# CAN_arduino_shield.net
KiCad netlist of a schematic drawn in EAGLE
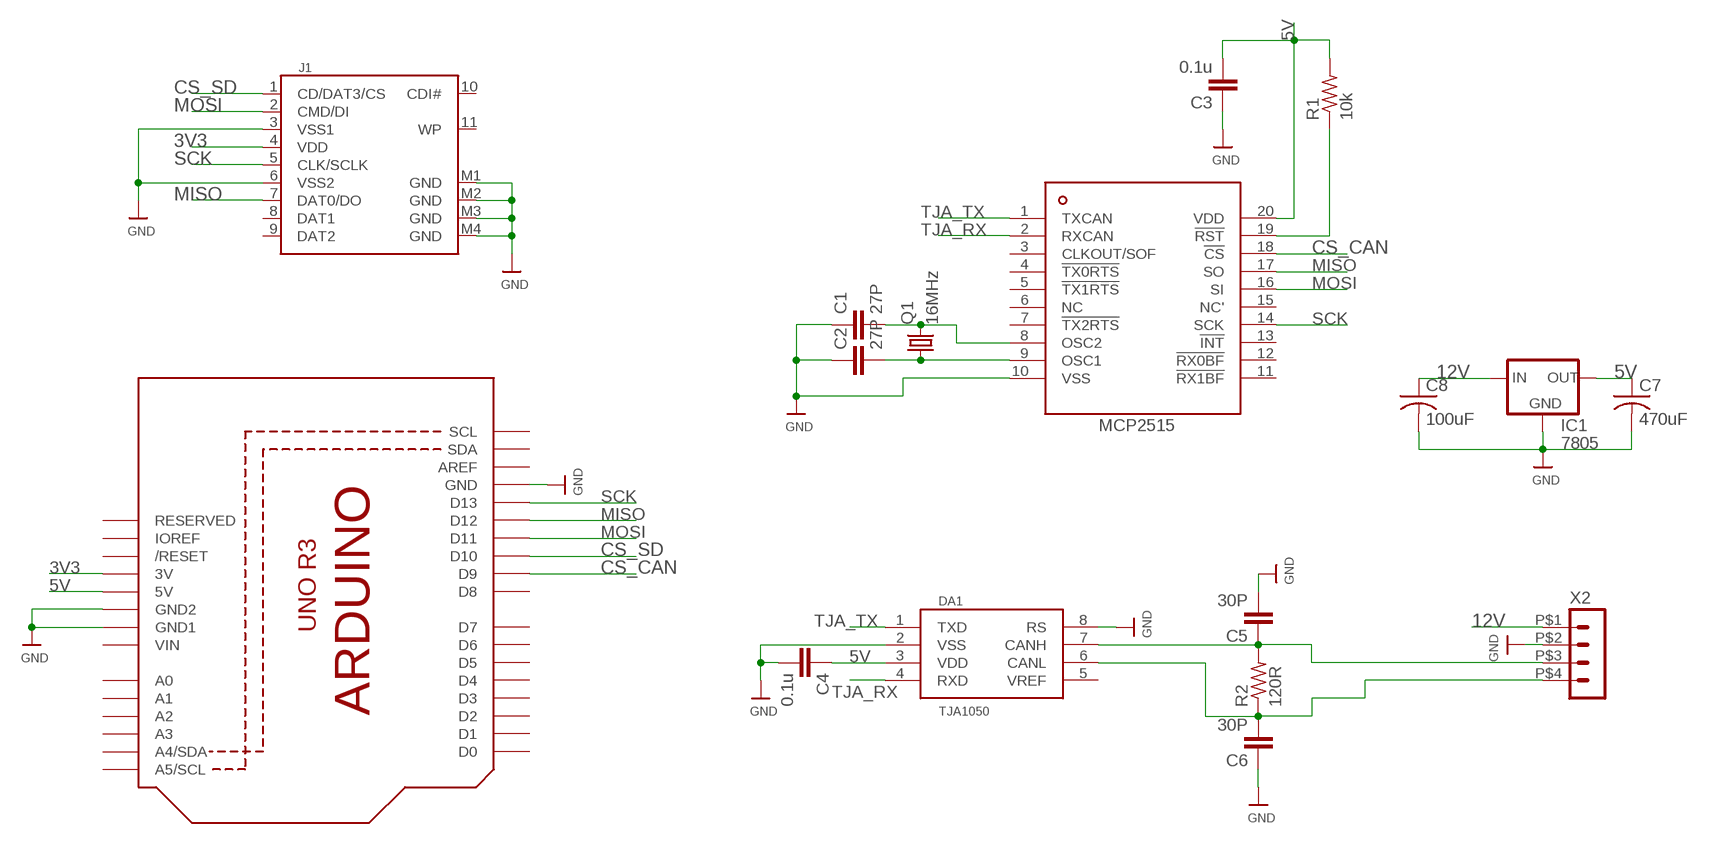
[diagram p0: schematic, sheet 1]

(export (version "E")
  (design (tool "Eeschema 10.0.6"))
  (components
    (comp (ref "C1")
      (value "27P")
      (footprint "eagle-import:C0805")
      (libsource (lib "eagle-import") (part "C-EUC0805"))
    )
    (comp (ref "C2")
      (value "27P")
      (footprint "eagle-import:C0805")
      (libsource (lib "eagle-import") (part "C-EUC0805"))
    )
    (comp (ref "C3")
      (value "0.1u")
      (footprint "eagle-import:C0805")
      (libsource (lib "eagle-import") (part "C-EUC0805"))
    )
    (comp (ref "C4")
      (value "0.1u")
      (footprint "eagle-import:C0805")
      (libsource (lib "eagle-import") (part "C-EUC0805"))
    )
    (comp (ref "C5")
      (value "30P")
      (footprint "eagle-import:C0805")
      (libsource (lib "eagle-import") (part "C-EUC0805"))
    )
    (comp (ref "C6")
      (value "30P")
      (footprint "eagle-import:C0805")
      (libsource (lib "eagle-import") (part "C-EUC0805"))
    )
    (comp (ref "C7")
      (value "470uF")
      (footprint "eagle-import:C025-050X050")
      (libsource (lib "eagle-import") (part "C-US025-050X050"))
    )
    (comp (ref "C8")
      (value "100uF")
      (footprint "eagle-import:C025-050X050")
      (libsource (lib "eagle-import") (part "C-US025-050X050"))
    )
    (comp (ref "DA1")
      (value "TJA1050")
      (footprint "eagle-import:SO08")
      (libsource (lib "eagle-import") (part "TJA1050"))
    )
    (comp (ref "IC1")
      (value "7805")
      (footprint "eagle-import:78XXS")
      (libsource (lib "eagle-import") (part "78XXS"))
    )
    (comp (ref "J1")
      (value "SDCARD")
      (footprint "eagle-import:SDCMF-10915W010")
      (libsource (lib "eagle-import") (part "SDCARD"))
    )
    (comp (ref "Q1")
      (value "16MHz")
      (footprint "eagle-import:HC49_S")
      (libsource (lib "eagle-import") (part "CRYSTALHC49S"))
    )
    (comp (ref "R1")
      (value "10k")
      (footprint "eagle-import:M0805")
      (libsource (lib "eagle-import") (part "R-US_M0805"))
    )
    (comp (ref "R2")
      (value "120R")
      (footprint "eagle-import:M0805")
      (libsource (lib "eagle-import") (part "R-US_M0805"))
    )
    (comp (ref "U$1")
      (value "MCP2515")
      (footprint "eagle-import:TSSOP20")
      (libsource (lib "eagle-import") (part "MCP2515"))
    )
    (comp (ref "U1")
      (value "ARDUINOR3-BPLACE")
      (footprint "eagle-import:ARDUINOR3-BPLACE")
      (libsource (lib "eagle-import") (part "ARDUINOR3-BPLACE"))
    )
    (comp (ref "X2")
      (value "HEADER_POS4_43045-0412")
      (footprint "eagle-import:43045-0412")
      (libsource (lib "eagle-import") (part "HEADER_POS4_?43045-0412"))
    )
  )
  (nets
    (net (code "1") (name "/3V3") (class "Default")
      (node (ref "J1") (pin "4") (pinfunction "VDD_4") (pintype "power_in"))
      (node (ref "U1") (pin "3V") (pinfunction "3V_3V") (pintype "power_in"))
    )
    (net (code "2") (name "/5V") (class "Default")
      (node (ref "C3") (pin "2") (pinfunction "2_2") (pintype "passive"))
      (node (ref "C4") (pin "1") (pinfunction "1_1") (pintype "passive"))
      (node (ref "C7") (pin "1") (pinfunction "1_1") (pintype "passive"))
      (node (ref "DA1") (pin "3") (pinfunction "VDD_3") (pintype "power_in"))
      (node (ref "IC1") (pin "OUT") (pinfunction "OUT_OUT") (pintype "passive"))
      (node (ref "R1") (pin "2") (pinfunction "2_2") (pintype "passive"))
      (node (ref "U$1") (pin "20") (pinfunction "VDD_20") (pintype "bidirectional"))
      (node (ref "U1") (pin "5V") (pinfunction "5V_5V") (pintype "power_in"))
    )
    (net (code "3") (name "/12V") (class "Default")
      (node (ref "C8") (pin "1") (pinfunction "1_1") (pintype "passive"))
      (node (ref "IC1") (pin "IN") (pinfunction "IN_IN") (pintype "input"))
      (node (ref "X2") (pin "P$1") (pinfunction "1_P$1") (pintype "passive"))
    )
    (net (code "4") (name "/CS_CAN") (class "Default")
      (node (ref "U$1") (pin "18") (pinfunction "~{CS}_18") (pintype "bidirectional"))
      (node (ref "U1") (pin "D9") (pinfunction "D9_D9") (pintype "bidirectional"))
    )
    (net (code "5") (name "/CS_SD") (class "Default")
      (node (ref "J1") (pin "1") (pinfunction "CD/DAT3/CS_1") (pintype "bidirectional"))
      (node (ref "U1") (pin "D10") (pinfunction "D10_D10") (pintype "bidirectional"))
    )
    (net (code "6") (name "/MISO") (class "Default")
      (node (ref "J1") (pin "7") (pinfunction "DAT0/DO_7") (pintype "bidirectional"))
      (node (ref "U$1") (pin "17") (pinfunction "SO_17") (pintype "bidirectional"))
      (node (ref "U1") (pin "D12") (pinfunction "D12_D12") (pintype "bidirectional"))
    )
    (net (code "7") (name "/MOSI") (class "Default")
      (node (ref "J1") (pin "2") (pinfunction "CMD/DI_2") (pintype "bidirectional"))
      (node (ref "U$1") (pin "16") (pinfunction "SI_16") (pintype "bidirectional"))
      (node (ref "U1") (pin "D11") (pinfunction "D11_D11") (pintype "bidirectional"))
    )
    (net (code "8") (name "/SCK") (class "Default")
      (node (ref "J1") (pin "5") (pinfunction "CLK/SCLK_5") (pintype "bidirectional"))
      (node (ref "U$1") (pin "14") (pinfunction "SCK_14") (pintype "bidirectional"))
      (node (ref "U1") (pin "D13") (pinfunction "D13_D13") (pintype "bidirectional"))
    )
    (net (code "9") (name "/TJA_RX") (class "Default")
      (node (ref "DA1") (pin "4") (pinfunction "RXD_4") (pintype "output"))
      (node (ref "U$1") (pin "2") (pinfunction "RXCAN_2") (pintype "bidirectional"))
    )
    (net (code "10") (name "/TJA_TX") (class "Default")
      (node (ref "DA1") (pin "1") (pinfunction "TXD_1") (pintype "input"))
      (node (ref "U$1") (pin "1") (pinfunction "TXCAN_1") (pintype "bidirectional"))
    )
    (net (code "11") (name "/VIN") (class "Default")
      (node (ref "U1") (pin "VIN") (pinfunction "VIN_VIN") (pintype "power_in"))
    )
    (net (code "12") (name "GND") (class "Default")
      (node (ref "C1") (pin "1") (pinfunction "1_1") (pintype "passive"))
      (node (ref "C2") (pin "1") (pinfunction "1_1") (pintype "passive"))
      (node (ref "C3") (pin "1") (pinfunction "1_1") (pintype "passive"))
      (node (ref "C4") (pin "2") (pinfunction "2_2") (pintype "passive"))
      (node (ref "C5") (pin "2") (pinfunction "2_2") (pintype "passive"))
      (node (ref "C6") (pin "1") (pinfunction "1_1") (pintype "passive"))
      (node (ref "C7") (pin "2") (pinfunction "2_2") (pintype "passive"))
      (node (ref "C8") (pin "2") (pinfunction "2_2") (pintype "passive"))
      (node (ref "DA1") (pin "2") (pinfunction "VSS_2") (pintype "power_in"))
      (node (ref "DA1") (pin "8") (pinfunction "RS_8") (pintype "input"))
      (node (ref "IC1") (pin "GND") (pinfunction "GND_GND") (pintype "input"))
      (node (ref "J1") (pin "3") (pinfunction "VSS1_3") (pintype "power_in"))
      (node (ref "J1") (pin "6") (pinfunction "VSS2_6") (pintype "power_in"))
      (node (ref "J1") (pin "M1") (pinfunction "GND_M1") (pintype "power_in"))
      (node (ref "J1") (pin "M2") (pinfunction "GND_M2") (pintype "power_in"))
      (node (ref "J1") (pin "M3") (pinfunction "GND_M3") (pintype "power_in"))
      (node (ref "J1") (pin "M4") (pinfunction "GND_M4") (pintype "power_in"))
      (node (ref "U$1") (pin "10") (pinfunction "VSS_10") (pintype "bidirectional"))
      (node (ref "U1") (pin "GND") (pinfunction "GND_GND") (pintype "power_in"))
      (node (ref "U1") (pin "GND1") (pinfunction "GND1_GND1") (pintype "power_in"))
      (node (ref "U1") (pin "GND2") (pinfunction "GND2_GND2") (pintype "power_in"))
      (node (ref "X2") (pin "P$2") (pinfunction "2_P$2") (pintype "passive"))
    )
    (net (code "13") (name "Net-(DA1-CANH)") (class "Default")
      (node (ref "C5") (pin "1") (pinfunction "1_1") (pintype "passive"))
      (node (ref "DA1") (pin "7") (pinfunction "CANH_7") (pintype "bidirectional"))
      (node (ref "R2") (pin "2") (pinfunction "2_2") (pintype "passive"))
      (node (ref "X2") (pin "P$3") (pinfunction "3_P$3") (pintype "passive"))
    )
    (net (code "14") (name "Net-(DA1-CANL)") (class "Default")
      (node (ref "C6") (pin "2") (pinfunction "2_2") (pintype "passive"))
      (node (ref "DA1") (pin "6") (pinfunction "CANL_6") (pintype "bidirectional"))
      (node (ref "R2") (pin "1") (pinfunction "1_1") (pintype "passive"))
      (node (ref "X2") (pin "P$4") (pinfunction "4_P$4") (pintype "passive"))
    )
    (net (code "15") (name "Net-(U$1-OSC1)") (class "Default")
      (node (ref "C2") (pin "2") (pinfunction "2_2") (pintype "passive"))
      (node (ref "Q1") (pin "1") (pinfunction "1_1") (pintype "passive"))
      (node (ref "U$1") (pin "9") (pinfunction "OSC1_9") (pintype "bidirectional"))
    )
    (net (code "16") (name "Net-(U$1-OSC2)") (class "Default")
      (node (ref "C1") (pin "2") (pinfunction "2_2") (pintype "passive"))
      (node (ref "Q1") (pin "2") (pinfunction "2_2") (pintype "passive"))
      (node (ref "U$1") (pin "8") (pinfunction "OSC2_8") (pintype "bidirectional"))
    )
    (net (code "17") (name "Net-(U$1-~{RST})") (class "Default")
      (node (ref "R1") (pin "1") (pinfunction "1_1") (pintype "passive"))
      (node (ref "U$1") (pin "19") (pinfunction "~{RST}_19") (pintype "bidirectional"))
    )
    (net (code "18") (name "unconnected-(DA1-VREF-Pad5)") (class "Default")
      (node (ref "DA1") (pin "5") (pinfunction "VREF_5") (pintype "passive"))
    )
    (net (code "19") (name "unconnected-(J1-CDI#-Pad10)") (class "Default")
      (node (ref "J1") (pin "10") (pinfunction "CDI#_10") (pintype "output"))
    )
    (net (code "20") (name "unconnected-(J1-DAT1-Pad8)") (class "Default")
      (node (ref "J1") (pin "8") (pinfunction "DAT1_8") (pintype "bidirectional"))
    )
    (net (code "21") (name "unconnected-(J1-DAT2-Pad9)") (class "Default")
      (node (ref "J1") (pin "9") (pinfunction "DAT2_9") (pintype "bidirectional"))
    )
    (net (code "22") (name "unconnected-(J1-WP-Pad11)") (class "Default")
      (node (ref "J1") (pin "11") (pinfunction "WP_11") (pintype "output"))
    )
    (net (code "23") (name "unconnected-(U$1-CLKOUT{slash}SOF-Pad3)") (class "Default")
      (node (ref "U$1") (pin "3") (pinfunction "CLKOUT/SOF_3") (pintype "bidirectional"))
    )
    (net (code "24") (name "unconnected-(U$1-NC'-Pad15)") (class "Default")
      (node (ref "U$1") (pin "15") (pinfunction "NC'_15") (pintype "bidirectional"))
    )
    (net (code "25") (name "unconnected-(U$1-NC-Pad6)") (class "Default")
      (node (ref "U$1") (pin "6") (pinfunction "NC_6") (pintype "bidirectional"))
    )
    (net (code "26") (name "unconnected-(U$1-~{INT}-Pad13)") (class "Default")
      (node (ref "U$1") (pin "13") (pinfunction "~{INT}_13") (pintype "bidirectional"))
    )
    (net (code "27") (name "unconnected-(U$1-~{RX0BF}-Pad12)") (class "Default")
      (node (ref "U$1") (pin "12") (pinfunction "~{RX0BF}_12") (pintype "bidirectional"))
    )
    (net (code "28") (name "unconnected-(U$1-~{RX1BF}-Pad11)") (class "Default")
      (node (ref "U$1") (pin "11") (pinfunction "~{RX1BF}_11") (pintype "bidirectional"))
    )
    (net (code "29") (name "unconnected-(U$1-~{TX0RTS}-Pad4)") (class "Default")
      (node (ref "U$1") (pin "4") (pinfunction "~{TX0RTS}_4") (pintype "bidirectional"))
    )
    (net (code "30") (name "unconnected-(U$1-~{TX1RTS}-Pad5)") (class "Default")
      (node (ref "U$1") (pin "5") (pinfunction "~{TX1RTS}_5") (pintype "bidirectional"))
    )
    (net (code "31") (name "unconnected-(U$1-~{TX2RTS}-Pad7)") (class "Default")
      (node (ref "U$1") (pin "7") (pinfunction "~{TX2RTS}_7") (pintype "bidirectional"))
    )
    (net (code "32") (name "unconnected-(U1-A4{slash}SDA-PadA4)") (class "Default")
      (node (ref "U1") (pin "A4") (pinfunction "A4/SDA_A4") (pintype "bidirectional"))
    )
    (net (code "33") (name "unconnected-(U1-A5{slash}SCL-PadA5)") (class "Default")
      (node (ref "U1") (pin "A5") (pinfunction "A5/SCL_A5") (pintype "bidirectional"))
    )
    (net (code "34") (name "unconnected-(U1-PadA0)") (class "Default")
      (node (ref "U1") (pin "A0") (pinfunction "A0_A0") (pintype "bidirectional"))
    )
    (net (code "35") (name "unconnected-(U1-PadA1)") (class "Default")
      (node (ref "U1") (pin "A1") (pinfunction "A1_A1") (pintype "bidirectional"))
    )
    (net (code "36") (name "unconnected-(U1-PadA2)") (class "Default")
      (node (ref "U1") (pin "A2") (pinfunction "A2_A2") (pintype "bidirectional"))
    )
    (net (code "37") (name "unconnected-(U1-PadA3)") (class "Default")
      (node (ref "U1") (pin "A3") (pinfunction "A3_A3") (pintype "bidirectional"))
    )
    (net (code "38") (name "unconnected-(U1-PadAREF)") (class "Default")
      (node (ref "U1") (pin "AREF") (pinfunction "AREF_AREF") (pintype "bidirectional"))
    )
    (net (code "39") (name "unconnected-(U1-PadD0)") (class "Default")
      (node (ref "U1") (pin "D0") (pinfunction "D0_D0") (pintype "bidirectional"))
    )
    (net (code "40") (name "unconnected-(U1-PadD1)") (class "Default")
      (node (ref "U1") (pin "D1") (pinfunction "D1_D1") (pintype "bidirectional"))
    )
    (net (code "41") (name "unconnected-(U1-PadD2)") (class "Default")
      (node (ref "U1") (pin "D2") (pinfunction "D2_D2") (pintype "bidirectional"))
    )
    (net (code "42") (name "unconnected-(U1-PadD3)") (class "Default")
      (node (ref "U1") (pin "D3") (pinfunction "D3_D3") (pintype "bidirectional"))
    )
    (net (code "43") (name "unconnected-(U1-PadD4)") (class "Default")
      (node (ref "U1") (pin "D4") (pinfunction "D4_D4") (pintype "bidirectional"))
    )
    (net (code "44") (name "unconnected-(U1-PadD5)") (class "Default")
      (node (ref "U1") (pin "D5") (pinfunction "D5_D5") (pintype "bidirectional"))
    )
    (net (code "45") (name "unconnected-(U1-PadD6)") (class "Default")
      (node (ref "U1") (pin "D6") (pinfunction "D6_D6") (pintype "bidirectional"))
    )
    (net (code "46") (name "unconnected-(U1-PadD7)") (class "Default")
      (node (ref "U1") (pin "D7") (pinfunction "D7_D7") (pintype "bidirectional"))
    )
    (net (code "47") (name "unconnected-(U1-PadD8)") (class "Default")
      (node (ref "U1") (pin "D8") (pinfunction "D8_D8") (pintype "bidirectional"))
    )
    (net (code "48") (name "unconnected-(U1-PadIOREF)") (class "Default")
      (node (ref "U1") (pin "IOREF") (pinfunction "IOREF_IOREF") (pintype "output"))
    )
    (net (code "49") (name "unconnected-(U1-PadRESERVED)") (class "Default")
      (node (ref "U1") (pin "RESERVED") (pinfunction "RESERVED_RESERVED") (pintype "no_connect"))
    )
    (net (code "50") (name "unconnected-(U1-PadSCL)") (class "Default")
      (node (ref "U1") (pin "SCL") (pinfunction "SCL_SCL") (pintype "bidirectional"))
    )
    (net (code "51") (name "unconnected-(U1-PadSDA)") (class "Default")
      (node (ref "U1") (pin "SDA") (pinfunction "SDA_SDA") (pintype "bidirectional"))
    )
    (net (code "52") (name "unconnected-(U1-{slash}RESET-PadRESET)") (class "Default")
      (node (ref "U1") (pin "RESET") (pinfunction "/RESET_RESET") (pintype "bidirectional"))
    )
  )
)
